# Pure_Sequencer.net
KiCad netlist of a schematic drawn in EAGLE
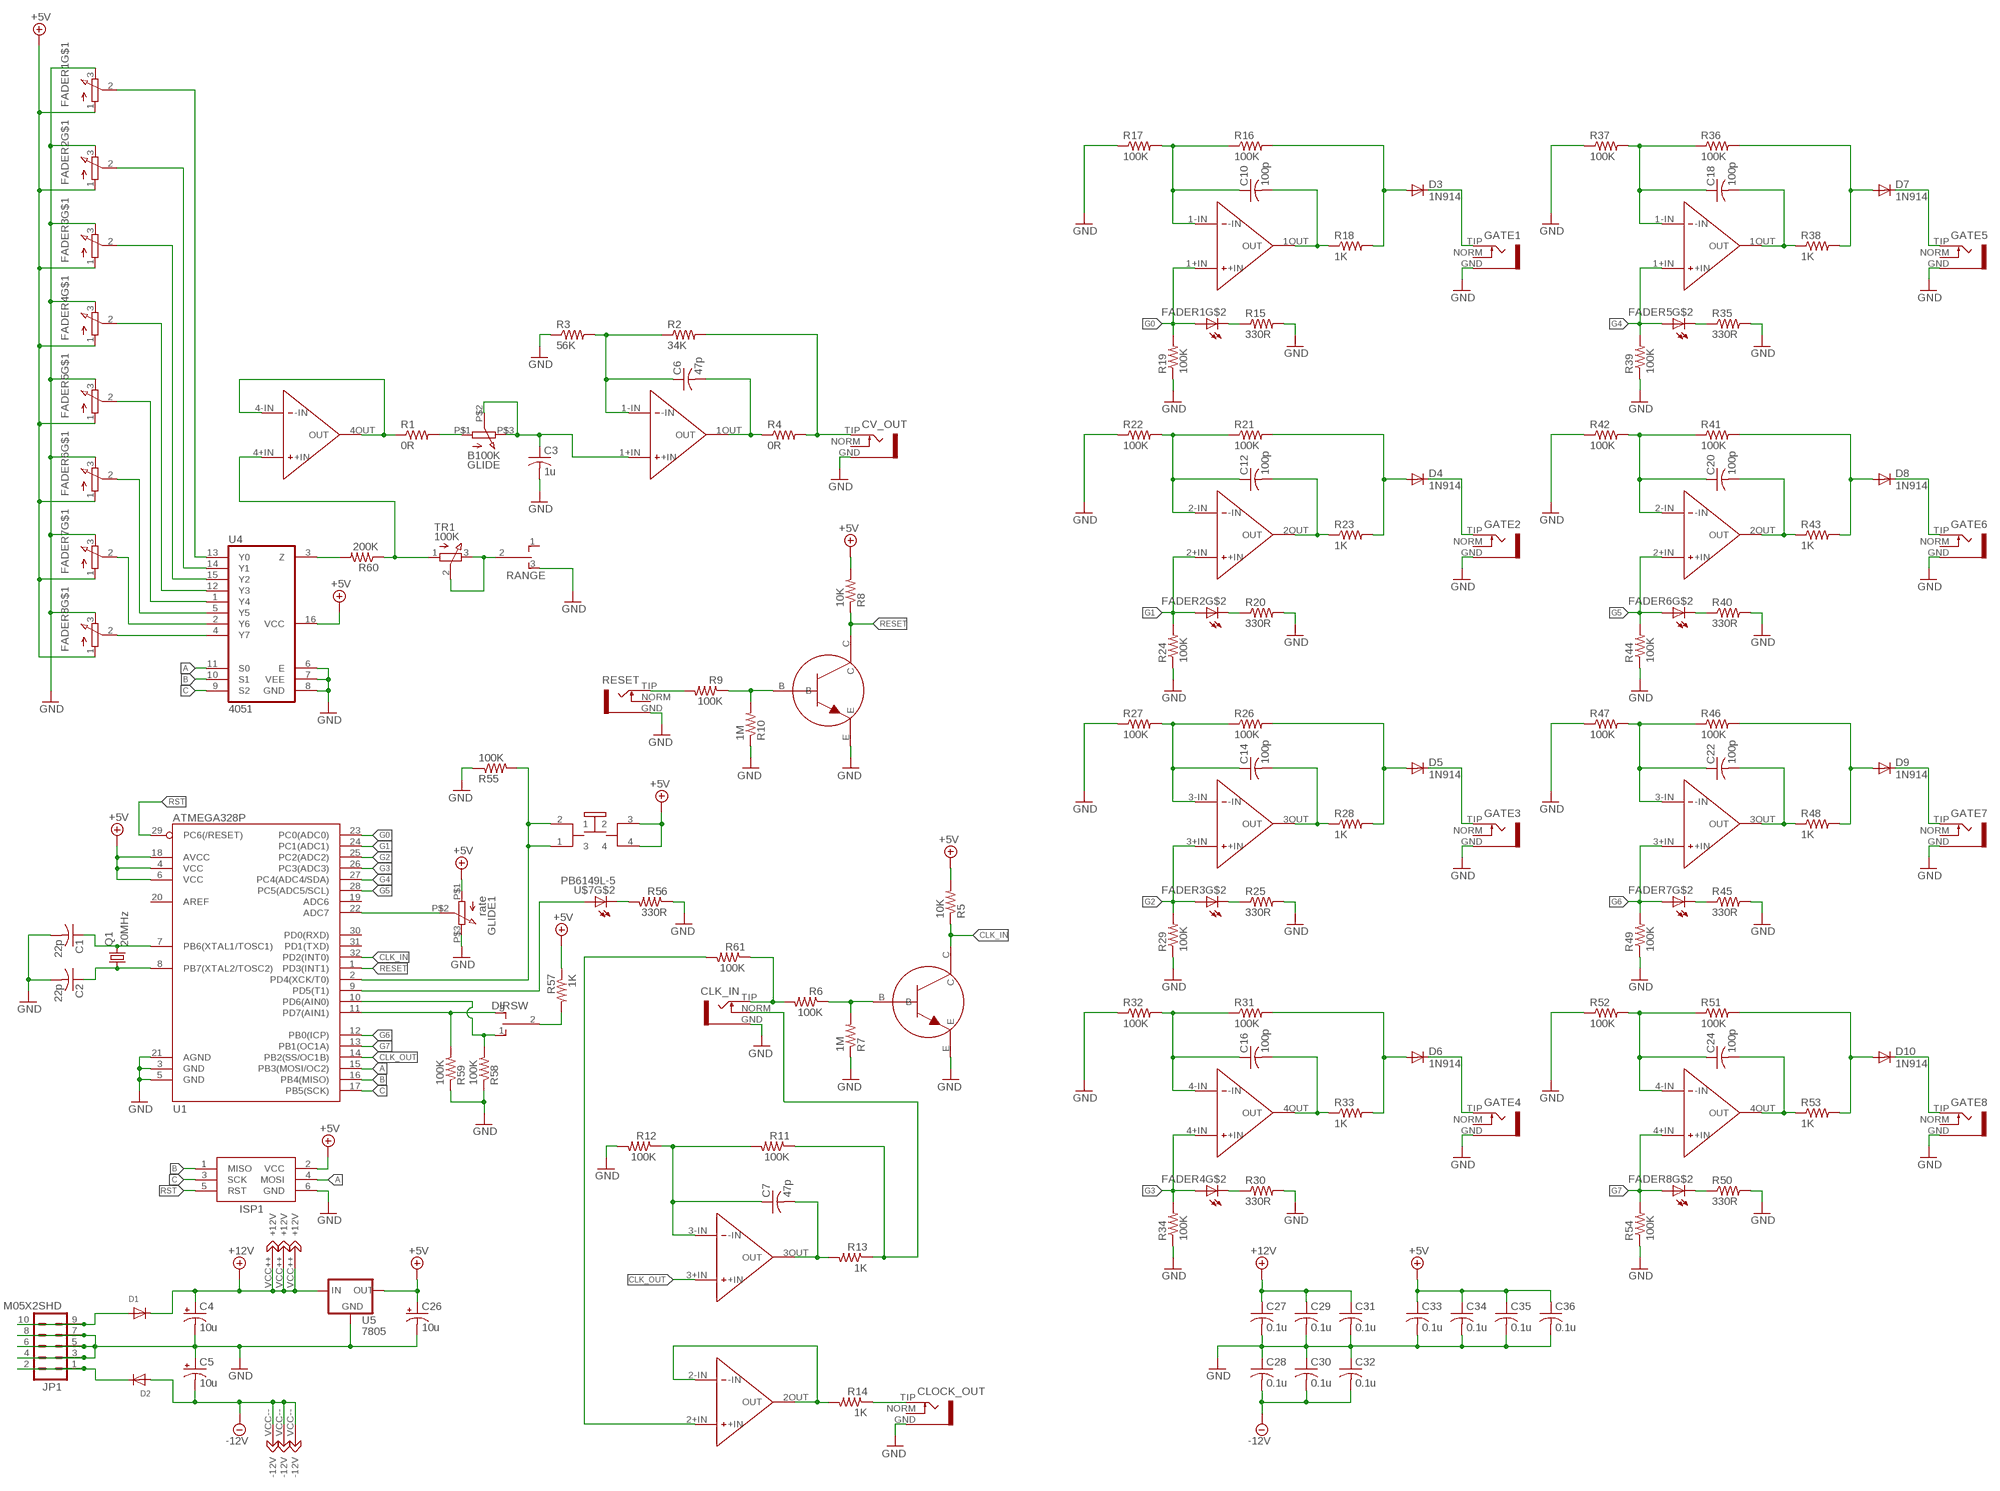
[diagram p0: schematic, sheet 1]

(export (version "E")
  (design (tool "Eeschema 10.0.6"))
  (components
    (comp (ref "C1")
      (value "22p")
      (footprint "eagle-import:C0805K")
      (libsource (lib "eagle-import") (part "C-USC0805K"))
    )
    (comp (ref "C2")
      (value "22p")
      (footprint "eagle-import:C0805K")
      (libsource (lib "eagle-import") (part "C-USC0805K"))
    )
    (comp (ref "C3")
      (value "1u")
      (footprint "eagle-import:C0805K")
      (libsource (lib "eagle-import") (part "C-USC0805K"))
    )
    (comp (ref "C4")
      (value "10u")
      (footprint "eagle-import:153CLV-0505")
      (libsource (lib "eagle-import") (part "CPOL-US153CLV-0505"))
    )
    (comp (ref "C5")
      (value "10u")
      (footprint "eagle-import:153CLV-0505")
      (libsource (lib "eagle-import") (part "CPOL-US153CLV-0505"))
    )
    (comp (ref "C6")
      (value "47p")
      (footprint "eagle-import:C0805K")
      (libsource (lib "eagle-import") (part "C-USC0805K"))
    )
    (comp (ref "C7")
      (value "47p")
      (footprint "eagle-import:C0805K")
      (libsource (lib "eagle-import") (part "C-USC0805K"))
    )
    (comp (ref "C10")
      (value "100p")
      (footprint "eagle-import:C0805K")
      (libsource (lib "eagle-import") (part "C-USC0805K"))
    )
    (comp (ref "C12")
      (value "100p")
      (footprint "eagle-import:C0805K")
      (libsource (lib "eagle-import") (part "C-USC0805K"))
    )
    (comp (ref "C14")
      (value "100p")
      (footprint "eagle-import:C0805K")
      (libsource (lib "eagle-import") (part "C-USC0805K"))
    )
    (comp (ref "C16")
      (value "100p")
      (footprint "eagle-import:C0805K")
      (libsource (lib "eagle-import") (part "C-USC0805K"))
    )
    (comp (ref "C18")
      (value "100p")
      (footprint "eagle-import:C0805K")
      (libsource (lib "eagle-import") (part "C-USC0805K"))
    )
    (comp (ref "C20")
      (value "100p")
      (footprint "eagle-import:C0805K")
      (libsource (lib "eagle-import") (part "C-USC0805K"))
    )
    (comp (ref "C22")
      (value "100p")
      (footprint "eagle-import:C0805K")
      (libsource (lib "eagle-import") (part "C-USC0805K"))
    )
    (comp (ref "C24")
      (value "100p")
      (footprint "eagle-import:C0805K")
      (libsource (lib "eagle-import") (part "C-USC0805K"))
    )
    (comp (ref "C26")
      (value "10u")
      (footprint "eagle-import:153CLV-0505")
      (libsource (lib "eagle-import") (part "CPOL-US153CLV-0505"))
    )
    (comp (ref "C27")
      (value "0.1u")
      (footprint "eagle-import:C0805K")
      (libsource (lib "eagle-import") (part "C-USC0805K"))
    )
    (comp (ref "C28")
      (value "0.1u")
      (footprint "eagle-import:C0805K")
      (libsource (lib "eagle-import") (part "C-USC0805K"))
    )
    (comp (ref "C29")
      (value "0.1u")
      (footprint "eagle-import:C0805K")
      (libsource (lib "eagle-import") (part "C-USC0805K"))
    )
    (comp (ref "C30")
      (value "0.1u")
      (footprint "eagle-import:C0805K")
      (libsource (lib "eagle-import") (part "C-USC0805K"))
    )
    (comp (ref "C31")
      (value "0.1u")
      (footprint "eagle-import:C0805K")
      (libsource (lib "eagle-import") (part "C-USC0805K"))
    )
    (comp (ref "C32")
      (value "0.1u")
      (footprint "eagle-import:C0805K")
      (libsource (lib "eagle-import") (part "C-USC0805K"))
    )
    (comp (ref "C33")
      (value "0.1u")
      (footprint "eagle-import:C0805K")
      (libsource (lib "eagle-import") (part "C-USC0805K"))
    )
    (comp (ref "C34")
      (value "0.1u")
      (footprint "eagle-import:C0805K")
      (libsource (lib "eagle-import") (part "C-USC0805K"))
    )
    (comp (ref "C35")
      (value "0.1u")
      (footprint "eagle-import:C0805K")
      (libsource (lib "eagle-import") (part "C-USC0805K"))
    )
    (comp (ref "C36")
      (value "0.1u")
      (footprint "eagle-import:C0805K")
      (libsource (lib "eagle-import") (part "C-USC0805K"))
    )
    (comp (ref "CLK_IN")
      (value "S_JACK")
      (footprint "eagle-import:S_JACK")
      (libsource (lib "eagle-import") (part "S_JACK"))
    )
    (comp (ref "CLOCK_OUT")
      (value "S_JACK")
      (footprint "eagle-import:S_JACK")
      (libsource (lib "eagle-import") (part "S_JACK"))
    )
    (comp (ref "CV_OUT")
      (value "S_JACK")
      (footprint "eagle-import:S_JACK")
      (libsource (lib "eagle-import") (part "S_JACK"))
    )
    (comp (ref "D1")
      (value "DIODESMA")
      (footprint "eagle-import:SMADIODE")
      (libsource (lib "eagle-import") (part "adafruit_DIODESMA"))
    )
    (comp (ref "D2")
      (value "DIODESMA")
      (footprint "eagle-import:SMADIODE")
      (libsource (lib "eagle-import") (part "adafruit_DIODESMA"))
    )
    (comp (ref "D3")
      (value "1N914")
      (footprint "eagle-import:SOD-323")
      (libsource (lib "eagle-import") (part "DIODESOD"))
    )
    (comp (ref "D4")
      (value "1N914")
      (footprint "eagle-import:SOD-323")
      (libsource (lib "eagle-import") (part "DIODESOD"))
    )
    (comp (ref "D5")
      (value "1N914")
      (footprint "eagle-import:SOD-323")
      (libsource (lib "eagle-import") (part "DIODESOD"))
    )
    (comp (ref "D6")
      (value "1N914")
      (footprint "eagle-import:SOD-323")
      (libsource (lib "eagle-import") (part "DIODESOD"))
    )
    (comp (ref "D7")
      (value "1N914")
      (footprint "eagle-import:SOD-323")
      (libsource (lib "eagle-import") (part "DIODESOD"))
    )
    (comp (ref "D8")
      (value "1N914")
      (footprint "eagle-import:SOD-323")
      (libsource (lib "eagle-import") (part "DIODESOD"))
    )
    (comp (ref "D9")
      (value "1N914")
      (footprint "eagle-import:SOD-323")
      (libsource (lib "eagle-import") (part "DIODESOD"))
    )
    (comp (ref "D10")
      (value "1N914")
      (footprint "eagle-import:SOD-323")
      (libsource (lib "eagle-import") (part "DIODESOD"))
    )
    (comp (ref "DIRSW")
      (value "TOGGLE_ON_OFF_ON")
      (footprint "eagle-import:TOGGLE_ON_OFF_ON")
      (libsource (lib "eagle-import") (part "TOGGLE_ON_OFF_ON"))
    )
    (comp (ref "FADER1")
      (value "LED_FADER")
      (footprint "eagle-import:LED_FADER")
      (libsource (lib "eagle-import") (part "LED_FADER"))
    )
    (comp (ref "FADER2")
      (value "LED_FADER")
      (footprint "eagle-import:LED_FADER")
      (libsource (lib "eagle-import") (part "LED_FADER"))
    )
    (comp (ref "FADER3")
      (value "LED_FADER")
      (footprint "eagle-import:LED_FADER")
      (libsource (lib "eagle-import") (part "LED_FADER"))
    )
    (comp (ref "FADER4")
      (value "LED_FADER")
      (footprint "eagle-import:LED_FADER")
      (libsource (lib "eagle-import") (part "LED_FADER"))
    )
    (comp (ref "FADER5")
      (value "LED_FADER")
      (footprint "eagle-import:LED_FADER")
      (libsource (lib "eagle-import") (part "LED_FADER"))
    )
    (comp (ref "FADER6")
      (value "LED_FADER")
      (footprint "eagle-import:LED_FADER")
      (libsource (lib "eagle-import") (part "LED_FADER"))
    )
    (comp (ref "FADER7")
      (value "LED_FADER")
      (footprint "eagle-import:LED_FADER")
      (libsource (lib "eagle-import") (part "LED_FADER"))
    )
    (comp (ref "FADER8")
      (value "LED_FADER")
      (footprint "eagle-import:LED_FADER")
      (libsource (lib "eagle-import") (part "LED_FADER"))
    )
    (comp (ref "GATE1")
      (value "S_JACK")
      (footprint "eagle-import:S_JACK")
      (libsource (lib "eagle-import") (part "S_JACK"))
    )
    (comp (ref "GATE2")
      (value "S_JACK")
      (footprint "eagle-import:S_JACK")
      (libsource (lib "eagle-import") (part "S_JACK"))
    )
    (comp (ref "GATE3")
      (value "S_JACK")
      (footprint "eagle-import:S_JACK")
      (libsource (lib "eagle-import") (part "S_JACK"))
    )
    (comp (ref "GATE4")
      (value "S_JACK")
      (footprint "eagle-import:S_JACK")
      (libsource (lib "eagle-import") (part "S_JACK"))
    )
    (comp (ref "GATE5")
      (value "S_JACK")
      (footprint "eagle-import:S_JACK")
      (libsource (lib "eagle-import") (part "S_JACK"))
    )
    (comp (ref "GATE6")
      (value "S_JACK")
      (footprint "eagle-import:S_JACK")
      (libsource (lib "eagle-import") (part "S_JACK"))
    )
    (comp (ref "GATE7")
      (value "S_JACK")
      (footprint "eagle-import:S_JACK")
      (libsource (lib "eagle-import") (part "S_JACK"))
    )
    (comp (ref "GATE8")
      (value "S_JACK")
      (footprint "eagle-import:S_JACK")
      (libsource (lib "eagle-import") (part "S_JACK"))
    )
    (comp (ref "GLIDE")
      (value "B100K")
      (footprint "eagle-import:Q-POT")
      (libsource (lib "eagle-import") (part "Q-POT"))
    )
    (comp (ref "GLIDE1")
      (value "rate")
      (footprint "eagle-import:Q-POT")
      (libsource (lib "eagle-import") (part "Q-POT"))
    )
    (comp (ref "ISP1")
      (value "AVRISP-6")
      (footprint "eagle-import:AVRISP")
      (libsource (lib "eagle-import") (part "AVRISP-6"))
    )
    (comp (ref "JP1")
      (value "M05X2SHD")
      (footprint "eagle-import:2X5-SHROUDED")
      (libsource (lib "eagle-import") (part "M05X2SHD"))
    )
    (comp (ref "Q1")
      (value "20MHz")
      (footprint "eagle-import:HC49UP")
      (libsource (lib "eagle-import") (part "CRYSTALHC49UP"))
    )
    (comp (ref "R1")
      (value "0R")
      (footprint "eagle-import:R0805")
      (libsource (lib "eagle-import") (part "R-US_R0805"))
    )
    (comp (ref "R2")
      (value "34K")
      (footprint "eagle-import:R0805")
      (libsource (lib "eagle-import") (part "R-US_R0805"))
    )
    (comp (ref "R3")
      (value "56K")
      (footprint "eagle-import:R0805")
      (libsource (lib "eagle-import") (part "R-US_R0805"))
    )
    (comp (ref "R4")
      (value "0R")
      (footprint "eagle-import:R0805")
      (libsource (lib "eagle-import") (part "R-US_R0805"))
    )
    (comp (ref "R5")
      (value "10K")
      (footprint "eagle-import:R0805")
      (libsource (lib "eagle-import") (part "R-US_R0805"))
    )
    (comp (ref "R6")
      (value "100K")
      (footprint "eagle-import:R0805")
      (libsource (lib "eagle-import") (part "R-US_R0805"))
    )
    (comp (ref "R7")
      (value "1M")
      (footprint "eagle-import:R0805")
      (libsource (lib "eagle-import") (part "R-US_R0805"))
    )
    (comp (ref "R8")
      (value "10K")
      (footprint "eagle-import:R0805")
      (libsource (lib "eagle-import") (part "R-US_R0805"))
    )
    (comp (ref "R9")
      (value "100K")
      (footprint "eagle-import:R0805")
      (libsource (lib "eagle-import") (part "R-US_R0805"))
    )
    (comp (ref "R10")
      (value "1M")
      (footprint "eagle-import:R0805")
      (libsource (lib "eagle-import") (part "R-US_R0805"))
    )
    (comp (ref "R11")
      (value "100K")
      (footprint "eagle-import:R0805")
      (libsource (lib "eagle-import") (part "R-US_R0805"))
    )
    (comp (ref "R12")
      (value "100K")
      (footprint "eagle-import:R0805")
      (libsource (lib "eagle-import") (part "R-US_R0805"))
    )
    (comp (ref "R13")
      (value "1K")
      (footprint "eagle-import:R0805")
      (libsource (lib "eagle-import") (part "R-US_R0805"))
    )
    (comp (ref "R14")
      (value "1K")
      (footprint "eagle-import:R0805")
      (libsource (lib "eagle-import") (part "R-US_R0805"))
    )
    (comp (ref "R15")
      (value "330R")
      (footprint "eagle-import:R0805")
      (libsource (lib "eagle-import") (part "R-US_R0805"))
    )
    (comp (ref "R16")
      (value "100K")
      (footprint "eagle-import:R0805")
      (libsource (lib "eagle-import") (part "R-US_R0805"))
    )
    (comp (ref "R17")
      (value "100K")
      (footprint "eagle-import:R0805")
      (libsource (lib "eagle-import") (part "R-US_R0805"))
    )
    (comp (ref "R18")
      (value "1K")
      (footprint "eagle-import:R0805")
      (libsource (lib "eagle-import") (part "R-US_R0805"))
    )
    (comp (ref "R19")
      (value "100K")
      (footprint "eagle-import:R0805")
      (libsource (lib "eagle-import") (part "R-US_R0805"))
    )
    (comp (ref "R20")
      (value "330R")
      (footprint "eagle-import:R0805")
      (libsource (lib "eagle-import") (part "R-US_R0805"))
    )
    (comp (ref "R21")
      (value "100K")
      (footprint "eagle-import:R0805")
      (libsource (lib "eagle-import") (part "R-US_R0805"))
    )
    (comp (ref "R22")
      (value "100K")
      (footprint "eagle-import:R0805")
      (libsource (lib "eagle-import") (part "R-US_R0805"))
    )
    (comp (ref "R23")
      (value "1K")
      (footprint "eagle-import:R0805")
      (libsource (lib "eagle-import") (part "R-US_R0805"))
    )
    (comp (ref "R24")
      (value "100K")
      (footprint "eagle-import:R0805")
      (libsource (lib "eagle-import") (part "R-US_R0805"))
    )
    (comp (ref "R25")
      (value "330R")
      (footprint "eagle-import:R0805")
      (libsource (lib "eagle-import") (part "R-US_R0805"))
    )
    (comp (ref "R26")
      (value "100K")
      (footprint "eagle-import:R0805")
      (libsource (lib "eagle-import") (part "R-US_R0805"))
    )
    (comp (ref "R27")
      (value "100K")
      (footprint "eagle-import:R0805")
      (libsource (lib "eagle-import") (part "R-US_R0805"))
    )
    (comp (ref "R28")
      (value "1K")
      (footprint "eagle-import:R0805")
      (libsource (lib "eagle-import") (part "R-US_R0805"))
    )
    (comp (ref "R29")
      (value "100K")
      (footprint "eagle-import:R0805")
      (libsource (lib "eagle-import") (part "R-US_R0805"))
    )
    (comp (ref "R30")
      (value "330R")
      (footprint "eagle-import:R0805")
      (libsource (lib "eagle-import") (part "R-US_R0805"))
    )
    (comp (ref "R31")
      (value "100K")
      (footprint "eagle-import:R0805")
      (libsource (lib "eagle-import") (part "R-US_R0805"))
    )
    (comp (ref "R32")
      (value "100K")
      (footprint "eagle-import:R0805")
      (libsource (lib "eagle-import") (part "R-US_R0805"))
    )
    (comp (ref "R33")
      (value "1K")
      (footprint "eagle-import:R0805")
      (libsource (lib "eagle-import") (part "R-US_R0805"))
    )
    (comp (ref "R34")
      (value "100K")
      (footprint "eagle-import:R0805")
      (libsource (lib "eagle-import") (part "R-US_R0805"))
    )
    (comp (ref "R35")
      (value "330R")
      (footprint "eagle-import:R0805")
      (libsource (lib "eagle-import") (part "R-US_R0805"))
    )
    (comp (ref "R36")
      (value "100K")
      (footprint "eagle-import:R0805")
      (libsource (lib "eagle-import") (part "R-US_R0805"))
    )
    (comp (ref "R37")
      (value "100K")
      (footprint "eagle-import:R0805")
      (libsource (lib "eagle-import") (part "R-US_R0805"))
    )
    (comp (ref "R38")
      (value "1K")
      (footprint "eagle-import:R0805")
      (libsource (lib "eagle-import") (part "R-US_R0805"))
    )
    (comp (ref "R39")
      (value "100K")
      (footprint "eagle-import:R0805")
      (libsource (lib "eagle-import") (part "R-US_R0805"))
    )
    (comp (ref "R40")
      (value "330R")
      (footprint "eagle-import:R0805")
      (libsource (lib "eagle-import") (part "R-US_R0805"))
    )
    (comp (ref "R41")
      (value "100K")
      (footprint "eagle-import:R0805")
      (libsource (lib "eagle-import") (part "R-US_R0805"))
    )
    (comp (ref "R42")
      (value "100K")
      (footprint "eagle-import:R0805")
      (libsource (lib "eagle-import") (part "R-US_R0805"))
    )
    (comp (ref "R43")
      (value "1K")
      (footprint "eagle-import:R0805")
      (libsource (lib "eagle-import") (part "R-US_R0805"))
    )
    (comp (ref "R44")
      (value "100K")
      (footprint "eagle-import:R0805")
      (libsource (lib "eagle-import") (part "R-US_R0805"))
    )
    (comp (ref "R45")
      (value "330R")
      (footprint "eagle-import:R0805")
      (libsource (lib "eagle-import") (part "R-US_R0805"))
    )
    (comp (ref "R46")
      (value "100K")
      (footprint "eagle-import:R0805")
      (libsource (lib "eagle-import") (part "R-US_R0805"))
    )
    (comp (ref "R47")
      (value "100K")
      (footprint "eagle-import:R0805")
      (libsource (lib "eagle-import") (part "R-US_R0805"))
    )
    (comp (ref "R48")
      (value "1K")
      (footprint "eagle-import:R0805")
      (libsource (lib "eagle-import") (part "R-US_R0805"))
    )
    (comp (ref "R49")
      (value "100K")
      (footprint "eagle-import:R0805")
      (libsource (lib "eagle-import") (part "R-US_R0805"))
    )
    (comp (ref "R50")
      (value "330R")
      (footprint "eagle-import:R0805")
      (libsource (lib "eagle-import") (part "R-US_R0805"))
    )
    (comp (ref "R51")
      (value "100K")
      (footprint "eagle-import:R0805")
      (libsource (lib "eagle-import") (part "R-US_R0805"))
    )
    (comp (ref "R52")
      (value "100K")
      (footprint "eagle-import:R0805")
      (libsource (lib "eagle-import") (part "R-US_R0805"))
    )
    (comp (ref "R53")
      (value "1K")
      (footprint "eagle-import:R0805")
      (libsource (lib "eagle-import") (part "R-US_R0805"))
    )
    (comp (ref "R54")
      (value "100K")
      (footprint "eagle-import:R0805")
      (libsource (lib "eagle-import") (part "R-US_R0805"))
    )
    (comp (ref "R55")
      (value "100K")
      (footprint "eagle-import:R0805")
      (libsource (lib "eagle-import") (part "R-US_R0805"))
    )
    (comp (ref "R56")
      (value "330R")
      (footprint "eagle-import:R0805")
      (libsource (lib "eagle-import") (part "R-US_R0805"))
    )
    (comp (ref "R57")
      (value "1K")
      (footprint "eagle-import:R0805")
      (libsource (lib "eagle-import") (part "R-US_R0805"))
    )
    (comp (ref "R58")
      (value "100K")
      (footprint "eagle-import:R0805")
      (libsource (lib "eagle-import") (part "R-US_R0805"))
    )
    (comp (ref "R59")
      (value "100K")
      (footprint "eagle-import:R0805")
      (libsource (lib "eagle-import") (part "R-US_R0805"))
    )
    (comp (ref "R60")
      (value "200K")
      (footprint "eagle-import:R0805")
      (libsource (lib "eagle-import") (part "R-US_R0805"))
    )
    (comp (ref "R61")
      (value "100K")
      (footprint "eagle-import:R0805")
      (libsource (lib "eagle-import") (part "R-US_R0805"))
    )
    (comp (ref "RANGE")
      (value "TOGGLE_ON_OFF_ON")
      (footprint "eagle-import:TOGGLE_ON_OFF_ON")
      (libsource (lib "eagle-import") (part "TOGGLE_ON_OFF_ON"))
    )
    (comp (ref "RESET")
      (value "S_JACK")
      (footprint "eagle-import:S_JACK")
      (libsource (lib "eagle-import") (part "S_JACK"))
    )
    (comp (ref "T1")
      (value "2N3904")
      (footprint "eagle-import:TRANSISTOR_SINGLE_N-TYPE")
      (libsource (lib "eagle-import") (part "TRANSISTOR_MMBT3904"))
    )
    (comp (ref "T2")
      (value "2N3904")
      (footprint "eagle-import:TRANSISTOR_SINGLE_N-TYPE")
      (libsource (lib "eagle-import") (part "TRANSISTOR_MMBT3904"))
    )
    (comp (ref "TR1")
      (value "100K")
      (footprint "eagle-import:TRIMMER_TH3")
      (libsource (lib "eagle-import") (part "TRIMMER_TH3"))
    )
    (comp (ref "U$7")
      (value "PB6149L-5")
      (footprint "eagle-import:PB6149L")
      (libsource (lib "eagle-import") (part "PB6149L-5"))
    )
    (comp (ref "U1")
      (value "ATMEGA328P")
      (footprint "eagle-import:TQFP32-08")
      (libsource (lib "eagle-import") (part "ATMEGA328_SMT"))
    )
    (comp (ref "U2")
      (value "QUAD_OPAMP")
      (footprint "eagle-import:QUAD_OPAMP")
      (libsource (lib "eagle-import") (part "QUAD_OPAMP"))
    )
    (comp (ref "U3")
      (value "QUAD_OPAMP")
      (footprint "eagle-import:QUAD_OPAMP")
      (libsource (lib "eagle-import") (part "QUAD_OPAMP"))
    )
    (comp (ref "U4")
      (value "4051")
      (footprint "eagle-import:N2222_ARRAY")
      (libsource (lib "eagle-import") (part "MUX!"))
    )
    (comp (ref "U5")
      (value "7805")
      (footprint "eagle-import:V-REG")
      (libsource (lib "eagle-import") (part "V-REG"))
    )
    (comp (ref "U6")
      (value "QUAD_OPAMP")
      (footprint "eagle-import:QUAD_OPAMP")
      (libsource (lib "eagle-import") (part "QUAD_OPAMP"))
    )
  )
  (nets
    (net (code "1") (name "+5V") (class "Default")
      (node (ref "C26") (pin "+") (pinfunction "+_+") (pintype "passive"))
      (node (ref "C33") (pin "1") (pinfunction "1_1") (pintype "passive"))
      (node (ref "C34") (pin "1") (pinfunction "1_1") (pintype "passive"))
      (node (ref "C35") (pin "1") (pinfunction "1_1") (pintype "passive"))
      (node (ref "C36") (pin "1") (pinfunction "1_1") (pintype "passive"))
      (node (ref "FADER1") (pin "1") (pinfunction "1_1") (pintype "passive"))
      (node (ref "FADER2") (pin "1") (pinfunction "1_1") (pintype "passive"))
      (node (ref "FADER3") (pin "1") (pinfunction "1_1") (pintype "passive"))
      (node (ref "FADER4") (pin "1") (pinfunction "1_1") (pintype "passive"))
      (node (ref "FADER5") (pin "1") (pinfunction "1_1") (pintype "passive"))
      (node (ref "FADER6") (pin "1") (pinfunction "1_1") (pintype "passive"))
      (node (ref "FADER7") (pin "1") (pinfunction "1_1") (pintype "passive"))
      (node (ref "FADER8") (pin "1") (pinfunction "1_1") (pintype "passive"))
      (node (ref "GLIDE1") (pin "P$1") (pinfunction "1_P$1") (pintype "passive"))
      (node (ref "ISP1") (pin "2") (pinfunction "VCC_2") (pintype "power_in"))
      (node (ref "R5") (pin "2") (pinfunction "2_2") (pintype "passive"))
      (node (ref "R57") (pin "1") (pinfunction "1_1") (pintype "passive"))
      (node (ref "R8") (pin "2") (pinfunction "2_2") (pintype "passive"))
      (node (ref "U$7") (pin "3") (pinfunction "2_3") (pintype "bidirectional"))
      (node (ref "U$7") (pin "4") (pinfunction "4_4") (pintype "bidirectional"))
      (node (ref "U1") (pin "18") (pinfunction "AVCC_18") (pintype "bidirectional"))
      (node (ref "U1") (pin "4") (pinfunction "VCC_4") (pintype "bidirectional"))
      (node (ref "U1") (pin "6") (pinfunction "VCC_6") (pintype "bidirectional"))
      (node (ref "U4") (pin "16") (pinfunction "VCC_16") (pintype "input"))
      (node (ref "U5") (pin "3") (pinfunction "OUT_3") (pintype "passive"))
    )
    (net (code "2") (name "+12V") (class "Default")
      (node (ref "C27") (pin "1") (pinfunction "1_1") (pintype "passive"))
      (node (ref "C29") (pin "1") (pinfunction "1_1") (pintype "passive"))
      (node (ref "C31") (pin "1") (pinfunction "1_1") (pintype "passive"))
      (node (ref "C4") (pin "+") (pinfunction "+_+") (pintype "passive"))
      (node (ref "D1") (pin "C") (pinfunction "C_C") (pintype "passive"))
      (node (ref "U2") (pin "VCC++") (pinfunction "+12V_VCC++") (pintype "bidirectional"))
      (node (ref "U3") (pin "VCC++") (pinfunction "+12V_VCC++") (pintype "bidirectional"))
      (node (ref "U5") (pin "1") (pinfunction "IN_1") (pintype "input"))
      (node (ref "U6") (pin "VCC++") (pinfunction "+12V_VCC++") (pintype "bidirectional"))
    )
    (net (code "3") (name "-12V") (class "Default")
      (node (ref "C28") (pin "2") (pinfunction "2_2") (pintype "passive"))
      (node (ref "C30") (pin "2") (pinfunction "2_2") (pintype "passive"))
      (node (ref "C32") (pin "2") (pinfunction "2_2") (pintype "passive"))
      (node (ref "C5") (pin "-") (pinfunction "-_-") (pintype "passive"))
      (node (ref "D2") (pin "A") (pinfunction "A_A") (pintype "passive"))
      (node (ref "U2") (pin "VCC--") (pinfunction "-12V_VCC--") (pintype "bidirectional"))
      (node (ref "U3") (pin "VCC--") (pinfunction "-12V_VCC--") (pintype "bidirectional"))
      (node (ref "U6") (pin "VCC--") (pinfunction "-12V_VCC--") (pintype "bidirectional"))
    )
    (net (code "4") (name "A") (class "Default")
      (node (ref "ISP1") (pin "4") (pinfunction "MOSI_4") (pintype "output"))
      (node (ref "U1") (pin "15") (pinfunction "PB3(MOSI/OC2)_15") (pintype "bidirectional"))
      (node (ref "U4") (pin "11") (pinfunction "S0_11") (pintype "input"))
    )
    (net (code "5") (name "B") (class "Default")
      (node (ref "ISP1") (pin "1") (pinfunction "MISO_1") (pintype "input"))
      (node (ref "U1") (pin "16") (pinfunction "PB4(MISO)_16") (pintype "bidirectional"))
      (node (ref "U4") (pin "10") (pinfunction "S1_10") (pintype "input"))
    )
    (net (code "6") (name "C") (class "Default")
      (node (ref "ISP1") (pin "3") (pinfunction "SCK_3") (pintype "output"))
      (node (ref "U1") (pin "17") (pinfunction "PB5(SCK)_17") (pintype "bidirectional"))
      (node (ref "U4") (pin "9") (pinfunction "S2_9") (pintype "input"))
    )
    (net (code "7") (name "CLK_IN") (class "Default")
      (node (ref "R5") (pin "1") (pinfunction "1_1") (pintype "passive"))
      (node (ref "T1") (pin "C") (pinfunction "C_C") (pintype "bidirectional"))
      (node (ref "U1") (pin "32") (pinfunction "PD2(INT0)_32") (pintype "bidirectional"))
    )
    (net (code "8") (name "CLK_OUT") (class "Default")
      (node (ref "U1") (pin "14") (pinfunction "PB2(SS/OC1B)_14") (pintype "bidirectional"))
      (node (ref "U6") (pin "3+IN") (pinfunction "+IN_3+IN") (pintype "bidirectional"))
    )
    (net (code "9") (name "G0") (class "Default")
      (node (ref "FADER1") (pin "A") (pinfunction "A_A") (pintype "passive"))
      (node (ref "R19") (pin "2") (pinfunction "2_2") (pintype "passive"))
      (node (ref "U1") (pin "23") (pinfunction "PC0(ADC0)_23") (pintype "bidirectional"))
      (node (ref "U2") (pin "1+IN") (pinfunction "+IN_1+IN") (pintype "bidirectional"))
    )
    (net (code "10") (name "G1") (class "Default")
      (node (ref "FADER2") (pin "A") (pinfunction "A_A") (pintype "passive"))
      (node (ref "R24") (pin "2") (pinfunction "2_2") (pintype "passive"))
      (node (ref "U1") (pin "24") (pinfunction "PC1(ADC1)_24") (pintype "bidirectional"))
      (node (ref "U2") (pin "2+IN") (pinfunction "+IN_2+IN") (pintype "bidirectional"))
    )
    (net (code "11") (name "G2") (class "Default")
      (node (ref "FADER3") (pin "A") (pinfunction "A_A") (pintype "passive"))
      (node (ref "R29") (pin "2") (pinfunction "2_2") (pintype "passive"))
      (node (ref "U1") (pin "25") (pinfunction "PC2(ADC2)_25") (pintype "bidirectional"))
      (node (ref "U2") (pin "3+IN") (pinfunction "+IN_3+IN") (pintype "bidirectional"))
    )
    (net (code "12") (name "G3") (class "Default")
      (node (ref "FADER4") (pin "A") (pinfunction "A_A") (pintype "passive"))
      (node (ref "R34") (pin "2") (pinfunction "2_2") (pintype "passive"))
      (node (ref "U1") (pin "26") (pinfunction "PC3(ADC3)_26") (pintype "bidirectional"))
      (node (ref "U2") (pin "4+IN") (pinfunction "+IN_4+IN") (pintype "bidirectional"))
    )
    (net (code "13") (name "G4") (class "Default")
      (node (ref "FADER5") (pin "A") (pinfunction "A_A") (pintype "passive"))
      (node (ref "R39") (pin "2") (pinfunction "2_2") (pintype "passive"))
      (node (ref "U1") (pin "27") (pinfunction "PC4(ADC4/SDA)_27") (pintype "bidirectional"))
      (node (ref "U3") (pin "1+IN") (pinfunction "+IN_1+IN") (pintype "bidirectional"))
    )
    (net (code "14") (name "G5") (class "Default")
      (node (ref "FADER6") (pin "A") (pinfunction "A_A") (pintype "passive"))
      (node (ref "R44") (pin "2") (pinfunction "2_2") (pintype "passive"))
      (node (ref "U1") (pin "28") (pinfunction "PC5(ADC5/SCL)_28") (pintype "bidirectional"))
      (node (ref "U3") (pin "2+IN") (pinfunction "+IN_2+IN") (pintype "bidirectional"))
    )
    (net (code "15") (name "G6") (class "Default")
      (node (ref "FADER7") (pin "A") (pinfunction "A_A") (pintype "passive"))
      (node (ref "R49") (pin "2") (pinfunction "2_2") (pintype "passive"))
      (node (ref "U1") (pin "12") (pinfunction "PB0(ICP)_12") (pintype "bidirectional"))
      (node (ref "U3") (pin "3+IN") (pinfunction "+IN_3+IN") (pintype "bidirectional"))
    )
    (net (code "16") (name "G7") (class "Default")
      (node (ref "FADER8") (pin "A") (pinfunction "A_A") (pintype "passive"))
      (node (ref "R54") (pin "2") (pinfunction "2_2") (pintype "passive"))
      (node (ref "U1") (pin "13") (pinfunction "PB1(OC1A)_13") (pintype "bidirectional"))
      (node (ref "U3") (pin "4+IN") (pinfunction "+IN_4+IN") (pintype "bidirectional"))
    )
    (net (code "17") (name "GND") (class "Default")
      (node (ref "C1") (pin "2") (pinfunction "2_2") (pintype "passive"))
      (node (ref "C2") (pin "2") (pinfunction "2_2") (pintype "passive"))
      (node (ref "C26") (pin "-") (pinfunction "-_-") (pintype "passive"))
      (node (ref "C27") (pin "2") (pinfunction "2_2") (pintype "passive"))
      (node (ref "C28") (pin "1") (pinfunction "1_1") (pintype "passive"))
      (node (ref "C29") (pin "2") (pinfunction "2_2") (pintype "passive"))
      (node (ref "C3") (pin "2") (pinfunction "2_2") (pintype "passive"))
      (node (ref "C30") (pin "1") (pinfunction "1_1") (pintype "passive"))
      (node (ref "C31") (pin "2") (pinfunction "2_2") (pintype "passive"))
      (node (ref "C32") (pin "1") (pinfunction "1_1") (pintype "passive"))
      (node (ref "C33") (pin "2") (pinfunction "2_2") (pintype "passive"))
      (node (ref "C34") (pin "2") (pinfunction "2_2") (pintype "passive"))
      (node (ref "C35") (pin "2") (pinfunction "2_2") (pintype "passive"))
      (node (ref "C36") (pin "2") (pinfunction "2_2") (pintype "passive"))
      (node (ref "C4") (pin "-") (pinfunction "-_-") (pintype "passive"))
      (node (ref "C5") (pin "+") (pinfunction "+_+") (pintype "passive"))
      (node (ref "CLK_IN") (pin "GND") (pinfunction "GND_GND") (pintype "passive"))
      (node (ref "CLOCK_OUT") (pin "GND") (pinfunction "GND_GND") (pintype "passive"))
      (node (ref "CV_OUT") (pin "GND") (pinfunction "GND_GND") (pintype "passive"))
      (node (ref "FADER1") (pin "3") (pinfunction "3_3") (pintype "passive"))
      (node (ref "FADER2") (pin "3") (pinfunction "3_3") (pintype "passive"))
      (node (ref "FADER3") (pin "3") (pinfunction "3_3") (pintype "passive"))
      (node (ref "FADER4") (pin "3") (pinfunction "3_3") (pintype "passive"))
      (node (ref "FADER5") (pin "3") (pinfunction "3_3") (pintype "passive"))
      (node (ref "FADER6") (pin "3") (pinfunction "3_3") (pintype "passive"))
      (node (ref "FADER7") (pin "3") (pinfunction "3_3") (pintype "passive"))
      (node (ref "FADER8") (pin "3") (pinfunction "3_3") (pintype "passive"))
      (node (ref "GATE1") (pin "GND") (pinfunction "GND_GND") (pintype "passive"))
      (node (ref "GATE2") (pin "GND") (pinfunction "GND_GND") (pintype "passive"))
      (node (ref "GATE3") (pin "GND") (pinfunction "GND_GND") (pintype "passive"))
      (node (ref "GATE4") (pin "GND") (pinfunction "GND_GND") (pintype "passive"))
      (node (ref "GATE5") (pin "GND") (pinfunction "GND_GND") (pintype "passive"))
      (node (ref "GATE6") (pin "GND") (pinfunction "GND_GND") (pintype "passive"))
      (node (ref "GATE7") (pin "GND") (pinfunction "GND_GND") (pintype "passive"))
      (node (ref "GATE8") (pin "GND") (pinfunction "GND_GND") (pintype "passive"))
      (node (ref "GLIDE1") (pin "P$3") (pinfunction "3_P$3") (pintype "passive"))
      (node (ref "ISP1") (pin "6") (pinfunction "GND_6") (pintype "power_in"))
      (node (ref "JP1") (pin "3") (pinfunction "3_3") (pintype "passive"))
      (node (ref "JP1") (pin "4") (pinfunction "4_4") (pintype "passive"))
      (node (ref "JP1") (pin "5") (pinfunction "5_5") (pintype "passive"))
      (node (ref "JP1") (pin "6") (pinfunction "6_6") (pintype "passive"))
      (node (ref "JP1") (pin "7") (pinfunction "7_7") (pintype "passive"))
      (node (ref "JP1") (pin "8") (pinfunction "8_8") (pintype "passive"))
      (node (ref "R10") (pin "1") (pinfunction "1_1") (pintype "passive"))
      (node (ref "R12") (pin "2") (pinfunction "2_2") (pintype "passive"))
      (node (ref "R15") (pin "2") (pinfunction "2_2") (pintype "passive"))
      (node (ref "R17") (pin "1") (pinfunction "1_1") (pintype "passive"))
      (node (ref "R19") (pin "1") (pinfunction "1_1") (pintype "passive"))
      (node (ref "R20") (pin "2") (pinfunction "2_2") (pintype "passive"))
      (node (ref "R22") (pin "1") (pinfunction "1_1") (pintype "passive"))
      (node (ref "R24") (pin "1") (pinfunction "1_1") (pintype "passive"))
      (node (ref "R25") (pin "2") (pinfunction "2_2") (pintype "passive"))
      (node (ref "R27") (pin "1") (pinfunction "1_1") (pintype "passive"))
      (node (ref "R29") (pin "1") (pinfunction "1_1") (pintype "passive"))
      (node (ref "R3") (pin "1") (pinfunction "1_1") (pintype "passive"))
      (node (ref "R30") (pin "2") (pinfunction "2_2") (pintype "passive"))
      (node (ref "R32") (pin "1") (pinfunction "1_1") (pintype "passive"))
      (node (ref "R34") (pin "1") (pinfunction "1_1") (pintype "passive"))
      (node (ref "R35") (pin "2") (pinfunction "2_2") (pintype "passive"))
      (node (ref "R37") (pin "1") (pinfunction "1_1") (pintype "passive"))
      (node (ref "R39") (pin "1") (pinfunction "1_1") (pintype "passive"))
      (node (ref "R40") (pin "2") (pinfunction "2_2") (pintype "passive"))
      (node (ref "R42") (pin "1") (pinfunction "1_1") (pintype "passive"))
      (node (ref "R44") (pin "1") (pinfunction "1_1") (pintype "passive"))
      (node (ref "R45") (pin "2") (pinfunction "2_2") (pintype "passive"))
      (node (ref "R47") (pin "1") (pinfunction "1_1") (pintype "passive"))
      (node (ref "R49") (pin "1") (pinfunction "1_1") (pintype "passive"))
      (node (ref "R50") (pin "2") (pinfunction "2_2") (pintype "passive"))
      (node (ref "R52") (pin "1") (pinfunction "1_1") (pintype "passive"))
      (node (ref "R54") (pin "1") (pinfunction "1_1") (pintype "passive"))
      (node (ref "R55") (pin "1") (pinfunction "1_1") (pintype "passive"))
      (node (ref "R56") (pin "1") (pinfunction "1_1") (pintype "passive"))
      (node (ref "R58") (pin "1") (pinfunction "1_1") (pintype "passive"))
      (node (ref "R59") (pin "1") (pinfunction "1_1") (pintype "passive"))
      (node (ref "R7") (pin "1") (pinfunction "1_1") (pintype "passive"))
      (node (ref "RANGE") (pin "3") (pinfunction "S_3") (pintype "passive"))
      (node (ref "RESET") (pin "GND") (pinfunction "GND_GND") (pintype "passive"))
      (node (ref "T1") (pin "E") (pinfunction "E_E") (pintype "bidirectional"))
      (node (ref "T2") (pin "E") (pinfunction "E_E") (pintype "bidirectional"))
      (node (ref "U1") (pin "21") (pinfunction "AGND_21") (pintype "bidirectional"))
      (node (ref "U1") (pin "3") (pinfunction "GND_3") (pintype "bidirectional"))
      (node (ref "U1") (pin "5") (pinfunction "GND_5") (pintype "bidirectional"))
      (node (ref "U4") (pin "6") (pinfunction "E_6") (pintype "bidirectional"))
      (node (ref "U4") (pin "7") (pinfunction "VEE_7") (pintype "bidirectional"))
      (node (ref "U4") (pin "8") (pinfunction "GND_8") (pintype "bidirectional"))
      (node (ref "U5") (pin "4") (pinfunction "GND_4") (pintype "input"))
    )
    (net (code "18") (name "Net-(CLK_IN-PadNORM)") (class "Default")
      (node (ref "CLK_IN") (pin "NORM") (pinfunction "NORM_NORM") (pintype "passive"))
      (node (ref "R11") (pin "1") (pinfunction "1_1") (pintype "passive"))
      (node (ref "R13") (pin "1") (pinfunction "1_1") (pintype "passive"))
    )
    (net (code "19") (name "Net-(CLK_IN-PadTIP)") (class "Default")
      (node (ref "CLK_IN") (pin "TIP") (pinfunction "TIP_TIP") (pintype "passive"))
      (node (ref "R6") (pin "2") (pinfunction "2_2") (pintype "passive"))
      (node (ref "R61") (pin "1") (pinfunction "1_1") (pintype "passive"))
    )
    (net (code "20") (name "Net-(CLOCK_OUT-PadTIP)") (class "Default")
      (node (ref "CLOCK_OUT") (pin "TIP") (pinfunction "TIP_TIP") (pintype "passive"))
      (node (ref "R14") (pin "1") (pinfunction "1_1") (pintype "passive"))
    )
    (net (code "21") (name "Net-(CV_OUT-PadTIP)") (class "Default")
      (node (ref "CV_OUT") (pin "TIP") (pinfunction "TIP_TIP") (pintype "passive"))
      (node (ref "R2") (pin "2") (pinfunction "2_2") (pintype "passive"))
      (node (ref "R4") (pin "2") (pinfunction "2_2") (pintype "passive"))
    )
    (net (code "22") (name "Net-(D1-PadA)") (class "Default")
      (node (ref "D1") (pin "A") (pinfunction "A_A") (pintype "passive"))
      (node (ref "JP1") (pin "10") (pinfunction "10_10") (pintype "passive"))
      (node (ref "JP1") (pin "9") (pinfunction "9_9") (pintype "passive"))
    )
    (net (code "23") (name "Net-(D2-PadC)") (class "Default")
      (node (ref "D2") (pin "C") (pinfunction "C_C") (pintype "passive"))
      (node (ref "JP1") (pin "1") (pinfunction "1_1") (pintype "passive"))
      (node (ref "JP1") (pin "2") (pinfunction "2_2") (pintype "passive"))
    )
    (net (code "24") (name "Net-(D3-A)") (class "Default")
      (node (ref "D3") (pin "2") (pinfunction "A_2") (pintype "passive"))
      (node (ref "R16") (pin "2") (pinfunction "2_2") (pintype "passive"))
      (node (ref "R18") (pin "2") (pinfunction "2_2") (pintype "passive"))
    )
    (net (code "25") (name "Net-(D3-C)") (class "Default")
      (node (ref "D3") (pin "1") (pinfunction "C_1") (pintype "passive"))
      (node (ref "GATE1") (pin "TIP") (pinfunction "TIP_TIP") (pintype "passive"))
    )
    (net (code "26") (name "Net-(D4-A)") (class "Default")
      (node (ref "D4") (pin "2") (pinfunction "A_2") (pintype "passive"))
      (node (ref "R21") (pin "2") (pinfunction "2_2") (pintype "passive"))
      (node (ref "R23") (pin "2") (pinfunction "2_2") (pintype "passive"))
    )
    (net (code "27") (name "Net-(D4-C)") (class "Default")
      (node (ref "D4") (pin "1") (pinfunction "C_1") (pintype "passive"))
      (node (ref "GATE2") (pin "TIP") (pinfunction "TIP_TIP") (pintype "passive"))
    )
    (net (code "28") (name "Net-(D5-A)") (class "Default")
      (node (ref "D5") (pin "2") (pinfunction "A_2") (pintype "passive"))
      (node (ref "R26") (pin "2") (pinfunction "2_2") (pintype "passive"))
      (node (ref "R28") (pin "2") (pinfunction "2_2") (pintype "passive"))
    )
    (net (code "29") (name "Net-(D5-C)") (class "Default")
      (node (ref "D5") (pin "1") (pinfunction "C_1") (pintype "passive"))
      (node (ref "GATE3") (pin "TIP") (pinfunction "TIP_TIP") (pintype "passive"))
    )
    (net (code "30") (name "Net-(D6-A)") (class "Default")
      (node (ref "D6") (pin "2") (pinfunction "A_2") (pintype "passive"))
      (node (ref "R31") (pin "2") (pinfunction "2_2") (pintype "passive"))
      (node (ref "R33") (pin "2") (pinfunction "2_2") (pintype "passive"))
    )
    (net (code "31") (name "Net-(D6-C)") (class "Default")
      (node (ref "D6") (pin "1") (pinfunction "C_1") (pintype "passive"))
      (node (ref "GATE4") (pin "TIP") (pinfunction "TIP_TIP") (pintype "passive"))
    )
    (net (code "32") (name "Net-(D7-A)") (class "Default")
      (node (ref "D7") (pin "2") (pinfunction "A_2") (pintype "passive"))
      (node (ref "R36") (pin "2") (pinfunction "2_2") (pintype "passive"))
      (node (ref "R38") (pin "2") (pinfunction "2_2") (pintype "passive"))
    )
    (net (code "33") (name "Net-(D7-C)") (class "Default")
      (node (ref "D7") (pin "1") (pinfunction "C_1") (pintype "passive"))
      (node (ref "GATE5") (pin "TIP") (pinfunction "TIP_TIP") (pintype "passive"))
    )
    (net (code "34") (name "Net-(D8-A)") (class "Default")
      (node (ref "D8") (pin "2") (pinfunction "A_2") (pintype "passive"))
      (node (ref "R41") (pin "2") (pinfunction "2_2") (pintype "passive"))
      (node (ref "R43") (pin "2") (pinfunction "2_2") (pintype "passive"))
    )
    (net (code "35") (name "Net-(D8-C)") (class "Default")
      (node (ref "D8") (pin "1") (pinfunction "C_1") (pintype "passive"))
      (node (ref "GATE6") (pin "TIP") (pinfunction "TIP_TIP") (pintype "passive"))
    )
    (net (code "36") (name "Net-(D9-A)") (class "Default")
      (node (ref "D9") (pin "2") (pinfunction "A_2") (pintype "passive"))
      (node (ref "R46") (pin "2") (pinfunction "2_2") (pintype "passive"))
      (node (ref "R48") (pin "2") (pinfunction "2_2") (pintype "passive"))
    )
    (net (code "37") (name "Net-(D9-C)") (class "Default")
      (node (ref "D9") (pin "1") (pinfunction "C_1") (pintype "passive"))
      (node (ref "GATE7") (pin "TIP") (pinfunction "TIP_TIP") (pintype "passive"))
    )
    (net (code "38") (name "Net-(D10-A)") (class "Default")
      (node (ref "D10") (pin "2") (pinfunction "A_2") (pintype "passive"))
      (node (ref "R51") (pin "2") (pinfunction "2_2") (pintype "passive"))
      (node (ref "R53") (pin "2") (pinfunction "2_2") (pintype "passive"))
    )
    (net (code "39") (name "Net-(D10-C)") (class "Default")
      (node (ref "D10") (pin "1") (pinfunction "C_1") (pintype "passive"))
      (node (ref "GATE8") (pin "TIP") (pinfunction "TIP_TIP") (pintype "passive"))
    )
    (net (code "40") (name "Net-(DIRSW-O)") (class "Default")
      (node (ref "DIRSW") (pin "1") (pinfunction "O_1") (pintype "passive"))
      (node (ref "R58") (pin "2") (pinfunction "2_2") (pintype "passive"))
      (node (ref "U1") (pin "10") (pinfunction "PD6(AIN0)_10") (pintype "bidirectional"))
    )
    (net (code "41") (name "Net-(DIRSW-P)") (class "Default")
      (node (ref "DIRSW") (pin "2") (pinfunction "P_2") (pintype "passive"))
      (node (ref "R57") (pin "2") (pinfunction "2_2") (pintype "passive"))
    )
    (net (code "42") (name "Net-(DIRSW-S)") (class "Default")
      (node (ref "DIRSW") (pin "3") (pinfunction "S_3") (pintype "passive"))
      (node (ref "R59") (pin "2") (pinfunction "2_2") (pintype "passive"))
      (node (ref "U1") (pin "11") (pinfunction "PD7(AIN1)_11") (pintype "bidirectional"))
    )
    (net (code "43") (name "Net-(FADER1B-C)") (class "Default")
      (node (ref "FADER1") (pin "K") (pinfunction "C_K") (pintype "passive"))
      (node (ref "R15") (pin "1") (pinfunction "1_1") (pintype "passive"))
    )
    (net (code "44") (name "Net-(FADER2B-C)") (class "Default")
      (node (ref "FADER2") (pin "K") (pinfunction "C_K") (pintype "passive"))
      (node (ref "R20") (pin "1") (pinfunction "1_1") (pintype "passive"))
    )
    (net (code "45") (name "Net-(FADER3B-C)") (class "Default")
      (node (ref "FADER3") (pin "K") (pinfunction "C_K") (pintype "passive"))
      (node (ref "R25") (pin "1") (pinfunction "1_1") (pintype "passive"))
    )
    (net (code "46") (name "Net-(FADER4B-C)") (class "Default")
      (node (ref "FADER4") (pin "K") (pinfunction "C_K") (pintype "passive"))
      (node (ref "R30") (pin "1") (pinfunction "1_1") (pintype "passive"))
    )
    (net (code "47") (name "Net-(FADER5B-C)") (class "Default")
      (node (ref "FADER5") (pin "K") (pinfunction "C_K") (pintype "passive"))
      (node (ref "R35") (pin "1") (pinfunction "1_1") (pintype "passive"))
    )
    (net (code "48") (name "Net-(FADER6B-C)") (class "Default")
      (node (ref "FADER6") (pin "K") (pinfunction "C_K") (pintype "passive"))
      (node (ref "R40") (pin "1") (pinfunction "1_1") (pintype "passive"))
    )
    (net (code "49") (name "Net-(FADER7B-C)") (class "Default")
      (node (ref "FADER7") (pin "K") (pinfunction "C_K") (pintype "passive"))
      (node (ref "R45") (pin "1") (pinfunction "1_1") (pintype "passive"))
    )
    (net (code "50") (name "Net-(FADER8B-C)") (class "Default")
      (node (ref "FADER8") (pin "K") (pinfunction "C_K") (pintype "passive"))
      (node (ref "R50") (pin "1") (pinfunction "1_1") (pintype "passive"))
    )
    (net (code "51") (name "Net-(GLIDE-1)") (class "Default")
      (node (ref "GLIDE") (pin "P$1") (pinfunction "1_P$1") (pintype "passive"))
      (node (ref "R1") (pin "2") (pinfunction "2_2") (pintype "passive"))
    )
    (net (code "52") (name "Net-(GLIDE-2)") (class "Default")
      (node (ref "C3") (pin "1") (pinfunction "1_1") (pintype "passive"))
      (node (ref "GLIDE") (pin "P$2") (pinfunction "2_P$2") (pintype "passive"))
      (node (ref "GLIDE") (pin "P$3") (pinfunction "3_P$3") (pintype "passive"))
      (node (ref "U6") (pin "1+IN") (pinfunction "+IN_1+IN") (pintype "bidirectional"))
    )
    (net (code "53") (name "Net-(GLIDE1-2)") (class "Default")
      (node (ref "GLIDE1") (pin "P$2") (pinfunction "2_P$2") (pintype "passive"))
      (node (ref "U1") (pin "22") (pinfunction "ADC7_22") (pintype "bidirectional"))
    )
    (net (code "54") (name "Net-(R6-Pad1)") (class "Default")
      (node (ref "R6") (pin "1") (pinfunction "1_1") (pintype "passive"))
      (node (ref "R7") (pin "2") (pinfunction "2_2") (pintype "passive"))
      (node (ref "T1") (pin "B") (pinfunction "B_B") (pintype "bidirectional"))
    )
    (net (code "55") (name "Net-(R9-Pad2)") (class "Default")
      (node (ref "R9") (pin "2") (pinfunction "2_2") (pintype "passive"))
      (node (ref "RESET") (pin "TIP") (pinfunction "TIP_TIP") (pintype "passive"))
    )
    (net (code "56") (name "Net-(R10-Pad2)") (class "Default")
      (node (ref "R10") (pin "2") (pinfunction "2_2") (pintype "passive"))
      (node (ref "R9") (pin "1") (pinfunction "1_1") (pintype "passive"))
      (node (ref "T2") (pin "B") (pinfunction "B_B") (pintype "bidirectional"))
    )
    (net (code "57") (name "Net-(RANGE-P)") (class "Default")
      (node (ref "RANGE") (pin "2") (pinfunction "P_2") (pintype "passive"))
      (node (ref "TR1") (pin "2") (pinfunction "2_2") (pintype "passive"))
      (node (ref "TR1") (pin "3") (pinfunction "3_3") (pintype "passive"))
    )
    (net (code "58") (name "Net-(U$7A-1)") (class "Default")
      (node (ref "R55") (pin "2") (pinfunction "2_2") (pintype "passive"))
      (node (ref "U$7") (pin "1") (pinfunction "3_1") (pintype "bidirectional"))
      (node (ref "U$7") (pin "2") (pinfunction "1_2") (pintype "bidirectional"))
      (node (ref "U1") (pin "2") (pinfunction "PD4(XCK/T0)_2") (pintype "bidirectional"))
    )
    (net (code "59") (name "Net-(U$7B-C)") (class "Default")
      (node (ref "R56") (pin "2") (pinfunction "2_2") (pintype "passive"))
      (node (ref "U$7") (pin "K") (pinfunction "C_K") (pintype "passive"))
    )
    (net (code "60") (name "Net-(U1-PB6(XTAL1{slash}TOSC1))") (class "Default")
      (node (ref "C1") (pin "1") (pinfunction "1_1") (pintype "passive"))
      (node (ref "Q1") (pin "2") (pinfunction "2_2") (pintype "passive"))
      (node (ref "U1") (pin "7") (pinfunction "PB6(XTAL1/TOSC1)_7") (pintype "bidirectional"))
    )
    (net (code "61") (name "Net-(U1-PB7(XTAL2{slash}TOSC2))") (class "Default")
      (node (ref "C2") (pin "1") (pinfunction "1_1") (pintype "passive"))
      (node (ref "Q1") (pin "1") (pinfunction "1_1") (pintype "passive"))
      (node (ref "U1") (pin "8") (pinfunction "PB7(XTAL2/TOSC2)_8") (pintype "bidirectional"))
    )
    (net (code "62") (name "Net-(U1-PD5(T1))") (class "Default")
      (node (ref "U$7") (pin "A") (pinfunction "A_A") (pintype "passive"))
      (node (ref "U1") (pin "9") (pinfunction "PD5(T1)_9") (pintype "bidirectional"))
    )
    (net (code "63") (name "Net-(U2A--IN)") (class "Default")
      (node (ref "C10") (pin "1") (pinfunction "1_1") (pintype "passive"))
      (node (ref "R16") (pin "1") (pinfunction "1_1") (pintype "passive"))
      (node (ref "R17") (pin "2") (pinfunction "2_2") (pintype "passive"))
      (node (ref "U2") (pin "1-IN") (pinfunction "-IN_1-IN") (pintype "bidirectional"))
    )
    (net (code "64") (name "Net-(U2A-OUT)") (class "Default")
      (node (ref "C10") (pin "2") (pinfunction "2_2") (pintype "passive"))
      (node (ref "R18") (pin "1") (pinfunction "1_1") (pintype "passive"))
      (node (ref "U2") (pin "1OUT") (pinfunction "OUT_1OUT") (pintype "bidirectional"))
    )
    (net (code "65") (name "Net-(U2B--IN)") (class "Default")
      (node (ref "C12") (pin "1") (pinfunction "1_1") (pintype "passive"))
      (node (ref "R21") (pin "1") (pinfunction "1_1") (pintype "passive"))
      (node (ref "R22") (pin "2") (pinfunction "2_2") (pintype "passive"))
      (node (ref "U2") (pin "2-IN") (pinfunction "-IN_2-IN") (pintype "bidirectional"))
    )
    (net (code "66") (name "Net-(U2B-OUT)") (class "Default")
      (node (ref "C12") (pin "2") (pinfunction "2_2") (pintype "passive"))
      (node (ref "R23") (pin "1") (pinfunction "1_1") (pintype "passive"))
      (node (ref "U2") (pin "2OUT") (pinfunction "OUT_2OUT") (pintype "bidirectional"))
    )
    (net (code "67") (name "Net-(U2C--IN)") (class "Default")
      (node (ref "C14") (pin "1") (pinfunction "1_1") (pintype "passive"))
      (node (ref "R26") (pin "1") (pinfunction "1_1") (pintype "passive"))
      (node (ref "R27") (pin "2") (pinfunction "2_2") (pintype "passive"))
      (node (ref "U2") (pin "3-IN") (pinfunction "-IN_3-IN") (pintype "bidirectional"))
    )
    (net (code "68") (name "Net-(U2C-OUT)") (class "Default")
      (node (ref "C14") (pin "2") (pinfunction "2_2") (pintype "passive"))
      (node (ref "R28") (pin "1") (pinfunction "1_1") (pintype "passive"))
      (node (ref "U2") (pin "3OUT") (pinfunction "OUT_3OUT") (pintype "bidirectional"))
    )
    (net (code "69") (name "Net-(U2D--IN)") (class "Default")
      (node (ref "C16") (pin "1") (pinfunction "1_1") (pintype "passive"))
      (node (ref "R31") (pin "1") (pinfunction "1_1") (pintype "passive"))
      (node (ref "R32") (pin "2") (pinfunction "2_2") (pintype "passive"))
      (node (ref "U2") (pin "4-IN") (pinfunction "-IN_4-IN") (pintype "bidirectional"))
    )
    (net (code "70") (name "Net-(U2D-OUT)") (class "Default")
      (node (ref "C16") (pin "2") (pinfunction "2_2") (pintype "passive"))
      (node (ref "R33") (pin "1") (pinfunction "1_1") (pintype "passive"))
      (node (ref "U2") (pin "4OUT") (pinfunction "OUT_4OUT") (pintype "bidirectional"))
    )
    (net (code "71") (name "Net-(U3A--IN)") (class "Default")
      (node (ref "C18") (pin "1") (pinfunction "1_1") (pintype "passive"))
      (node (ref "R36") (pin "1") (pinfunction "1_1") (pintype "passive"))
      (node (ref "R37") (pin "2") (pinfunction "2_2") (pintype "passive"))
      (node (ref "U3") (pin "1-IN") (pinfunction "-IN_1-IN") (pintype "bidirectional"))
    )
    (net (code "72") (name "Net-(U3A-OUT)") (class "Default")
      (node (ref "C18") (pin "2") (pinfunction "2_2") (pintype "passive"))
      (node (ref "R38") (pin "1") (pinfunction "1_1") (pintype "passive"))
      (node (ref "U3") (pin "1OUT") (pinfunction "OUT_1OUT") (pintype "bidirectional"))
    )
    (net (code "73") (name "Net-(U3B--IN)") (class "Default")
      (node (ref "C20") (pin "1") (pinfunction "1_1") (pintype "passive"))
      (node (ref "R41") (pin "1") (pinfunction "1_1") (pintype "passive"))
      (node (ref "R42") (pin "2") (pinfunction "2_2") (pintype "passive"))
      (node (ref "U3") (pin "2-IN") (pinfunction "-IN_2-IN") (pintype "bidirectional"))
    )
    (net (code "74") (name "Net-(U3B-OUT)") (class "Default")
      (node (ref "C20") (pin "2") (pinfunction "2_2") (pintype "passive"))
      (node (ref "R43") (pin "1") (pinfunction "1_1") (pintype "passive"))
      (node (ref "U3") (pin "2OUT") (pinfunction "OUT_2OUT") (pintype "bidirectional"))
    )
    (net (code "75") (name "Net-(U3C--IN)") (class "Default")
      (node (ref "C22") (pin "1") (pinfunction "1_1") (pintype "passive"))
      (node (ref "R46") (pin "1") (pinfunction "1_1") (pintype "passive"))
      (node (ref "R47") (pin "2") (pinfunction "2_2") (pintype "passive"))
      (node (ref "U3") (pin "3-IN") (pinfunction "-IN_3-IN") (pintype "bidirectional"))
    )
    (net (code "76") (name "Net-(U3C-OUT)") (class "Default")
      (node (ref "C22") (pin "2") (pinfunction "2_2") (pintype "passive"))
      (node (ref "R48") (pin "1") (pinfunction "1_1") (pintype "passive"))
      (node (ref "U3") (pin "3OUT") (pinfunction "OUT_3OUT") (pintype "bidirectional"))
    )
    (net (code "77") (name "Net-(U3D--IN)") (class "Default")
      (node (ref "C24") (pin "1") (pinfunction "1_1") (pintype "passive"))
      (node (ref "R51") (pin "1") (pinfunction "1_1") (pintype "passive"))
      (node (ref "R52") (pin "2") (pinfunction "2_2") (pintype "passive"))
      (node (ref "U3") (pin "4-IN") (pinfunction "-IN_4-IN") (pintype "bidirectional"))
    )
    (net (code "78") (name "Net-(U3D-OUT)") (class "Default")
      (node (ref "C24") (pin "2") (pinfunction "2_2") (pintype "passive"))
      (node (ref "R53") (pin "1") (pinfunction "1_1") (pintype "passive"))
      (node (ref "U3") (pin "4OUT") (pinfunction "OUT_4OUT") (pintype "bidirectional"))
    )
    (net (code "79") (name "Net-(U4-Y0)") (class "Default")
      (node (ref "FADER1") (pin "2") (pinfunction "2_2") (pintype "passive"))
      (node (ref "U4") (pin "13") (pinfunction "Y0_13") (pintype "bidirectional"))
    )
    (net (code "80") (name "Net-(U4-Y1)") (class "Default")
      (node (ref "FADER2") (pin "2") (pinfunction "2_2") (pintype "passive"))
      (node (ref "U4") (pin "14") (pinfunction "Y1_14") (pintype "bidirectional"))
    )
    (net (code "81") (name "Net-(U4-Y2)") (class "Default")
      (node (ref "FADER3") (pin "2") (pinfunction "2_2") (pintype "passive"))
      (node (ref "U4") (pin "15") (pinfunction "Y2_15") (pintype "bidirectional"))
    )
    (net (code "82") (name "Net-(U4-Y3)") (class "Default")
      (node (ref "FADER4") (pin "2") (pinfunction "2_2") (pintype "passive"))
      (node (ref "U4") (pin "12") (pinfunction "Y3_12") (pintype "bidirectional"))
    )
    (net (code "83") (name "Net-(U4-Y4)") (class "Default")
      (node (ref "FADER5") (pin "2") (pinfunction "2_2") (pintype "passive"))
      (node (ref "U4") (pin "1") (pinfunction "Y4_1") (pintype "bidirectional"))
    )
    (net (code "84") (name "Net-(U4-Y5)") (class "Default")
      (node (ref "FADER6") (pin "2") (pinfunction "2_2") (pintype "passive"))
      (node (ref "U4") (pin "5") (pinfunction "Y5_5") (pintype "bidirectional"))
    )
    (net (code "85") (name "Net-(U4-Y6)") (class "Default")
      (node (ref "FADER7") (pin "2") (pinfunction "2_2") (pintype "passive"))
      (node (ref "U4") (pin "2") (pinfunction "Y6_2") (pintype "bidirectional"))
    )
    (net (code "86") (name "Net-(U4-Y7)") (class "Default")
      (node (ref "FADER8") (pin "2") (pinfunction "2_2") (pintype "passive"))
      (node (ref "U4") (pin "4") (pinfunction "Y7_4") (pintype "bidirectional"))
    )
    (net (code "87") (name "Net-(U4-Z)") (class "Default")
      (node (ref "R60") (pin "2") (pinfunction "2_2") (pintype "passive"))
      (node (ref "U4") (pin "3") (pinfunction "Z_3") (pintype "bidirectional"))
    )
    (net (code "88") (name "Net-(U6A--IN)") (class "Default")
      (node (ref "C6") (pin "1") (pinfunction "1_1") (pintype "passive"))
      (node (ref "R2") (pin "1") (pinfunction "1_1") (pintype "passive"))
      (node (ref "R3") (pin "2") (pinfunction "2_2") (pintype "passive"))
      (node (ref "U6") (pin "1-IN") (pinfunction "-IN_1-IN") (pintype "bidirectional"))
    )
    (net (code "89") (name "Net-(U6A-OUT)") (class "Default")
      (node (ref "C6") (pin "2") (pinfunction "2_2") (pintype "passive"))
      (node (ref "R4") (pin "1") (pinfunction "1_1") (pintype "passive"))
      (node (ref "U6") (pin "1OUT") (pinfunction "OUT_1OUT") (pintype "bidirectional"))
    )
    (net (code "90") (name "Net-(U6B-+IN)") (class "Default")
      (node (ref "R61") (pin "2") (pinfunction "2_2") (pintype "passive"))
      (node (ref "U6") (pin "2+IN") (pinfunction "+IN_2+IN") (pintype "bidirectional"))
    )
    (net (code "91") (name "Net-(U6B--IN)") (class "Default")
      (node (ref "R14") (pin "2") (pinfunction "2_2") (pintype "passive"))
      (node (ref "U6") (pin "2-IN") (pinfunction "-IN_2-IN") (pintype "bidirectional"))
      (node (ref "U6") (pin "2OUT") (pinfunction "OUT_2OUT") (pintype "bidirectional"))
    )
    (net (code "92") (name "Net-(U6C--IN)") (class "Default")
      (node (ref "C7") (pin "1") (pinfunction "1_1") (pintype "passive"))
      (node (ref "R11") (pin "2") (pinfunction "2_2") (pintype "passive"))
      (node (ref "R12") (pin "1") (pinfunction "1_1") (pintype "passive"))
      (node (ref "U6") (pin "3-IN") (pinfunction "-IN_3-IN") (pintype "bidirectional"))
    )
    (net (code "93") (name "Net-(U6C-OUT)") (class "Default")
      (node (ref "C7") (pin "2") (pinfunction "2_2") (pintype "passive"))
      (node (ref "R13") (pin "2") (pinfunction "2_2") (pintype "passive"))
      (node (ref "U6") (pin "3OUT") (pinfunction "OUT_3OUT") (pintype "bidirectional"))
    )
    (net (code "94") (name "Net-(U6D-+IN)") (class "Default")
      (node (ref "R60") (pin "1") (pinfunction "1_1") (pintype "passive"))
      (node (ref "TR1") (pin "1") (pinfunction "1_1") (pintype "passive"))
      (node (ref "U6") (pin "4+IN") (pinfunction "+IN_4+IN") (pintype "bidirectional"))
    )
    (net (code "95") (name "Net-(U6D--IN)") (class "Default")
      (node (ref "R1") (pin "1") (pinfunction "1_1") (pintype "passive"))
      (node (ref "U6") (pin "4-IN") (pinfunction "-IN_4-IN") (pintype "bidirectional"))
      (node (ref "U6") (pin "4OUT") (pinfunction "OUT_4OUT") (pintype "bidirectional"))
    )
    (net (code "96") (name "RESET") (class "Default")
      (node (ref "R8") (pin "1") (pinfunction "1_1") (pintype "passive"))
      (node (ref "T2") (pin "C") (pinfunction "C_C") (pintype "bidirectional"))
      (node (ref "U1") (pin "1") (pinfunction "PD3(INT1)_1") (pintype "bidirectional"))
    )
    (net (code "97") (name "RST") (class "Default")
      (node (ref "ISP1") (pin "5") (pinfunction "RST_5") (pintype "output"))
      (node (ref "U1") (pin "29") (pinfunction "PC6(/RESET)_29") (pintype "bidirectional"))
    )
    (net (code "98") (name "unconnected-(CLOCK_OUT-PadNORM)") (class "Default")
      (node (ref "CLOCK_OUT") (pin "NORM") (pinfunction "NORM_NORM") (pintype "passive"))
    )
    (net (code "99") (name "unconnected-(CV_OUT-PadNORM)") (class "Default")
      (node (ref "CV_OUT") (pin "NORM") (pinfunction "NORM_NORM") (pintype "passive"))
    )
    (net (code "100") (name "unconnected-(GATE1-PadNORM)") (class "Default")
      (node (ref "GATE1") (pin "NORM") (pinfunction "NORM_NORM") (pintype "passive"))
    )
    (net (code "101") (name "unconnected-(GATE2-PadNORM)") (class "Default")
      (node (ref "GATE2") (pin "NORM") (pinfunction "NORM_NORM") (pintype "passive"))
    )
    (net (code "102") (name "unconnected-(GATE3-PadNORM)") (class "Default")
      (node (ref "GATE3") (pin "NORM") (pinfunction "NORM_NORM") (pintype "passive"))
    )
    (net (code "103") (name "unconnected-(GATE4-PadNORM)") (class "Default")
      (node (ref "GATE4") (pin "NORM") (pinfunction "NORM_NORM") (pintype "passive"))
    )
    (net (code "104") (name "unconnected-(GATE5-PadNORM)") (class "Default")
      (node (ref "GATE5") (pin "NORM") (pinfunction "NORM_NORM") (pintype "passive"))
    )
    (net (code "105") (name "unconnected-(GATE6-PadNORM)") (class "Default")
      (node (ref "GATE6") (pin "NORM") (pinfunction "NORM_NORM") (pintype "passive"))
    )
    (net (code "106") (name "unconnected-(GATE7-PadNORM)") (class "Default")
      (node (ref "GATE7") (pin "NORM") (pinfunction "NORM_NORM") (pintype "passive"))
    )
    (net (code "107") (name "unconnected-(GATE8-PadNORM)") (class "Default")
      (node (ref "GATE8") (pin "NORM") (pinfunction "NORM_NORM") (pintype "passive"))
    )
    (net (code "108") (name "unconnected-(RANGE-O-Pad1)") (class "Default")
      (node (ref "RANGE") (pin "1") (pinfunction "O_1") (pintype "passive"))
    )
    (net (code "109") (name "unconnected-(RESET-PadNORM)") (class "Default")
      (node (ref "RESET") (pin "NORM") (pinfunction "NORM_NORM") (pintype "passive"))
    )
    (net (code "110") (name "unconnected-(U1-ADC6-Pad19)") (class "Default")
      (node (ref "U1") (pin "19") (pinfunction "ADC6_19") (pintype "bidirectional"))
    )
    (net (code "111") (name "unconnected-(U1-AREF-Pad20)") (class "Default")
      (node (ref "U1") (pin "20") (pinfunction "AREF_20") (pintype "bidirectional"))
    )
    (net (code "112") (name "unconnected-(U1-PD0(RXD)-Pad30)") (class "Default")
      (node (ref "U1") (pin "30") (pinfunction "PD0(RXD)_30") (pintype "bidirectional"))
    )
    (net (code "113") (name "unconnected-(U1-PD1(TXD)-Pad31)") (class "Default")
      (node (ref "U1") (pin "31") (pinfunction "PD1(TXD)_31") (pintype "bidirectional"))
    )
  )
)
